# BlaszczakPI.net
KiCad netlist of a schematic drawn in EAGLE
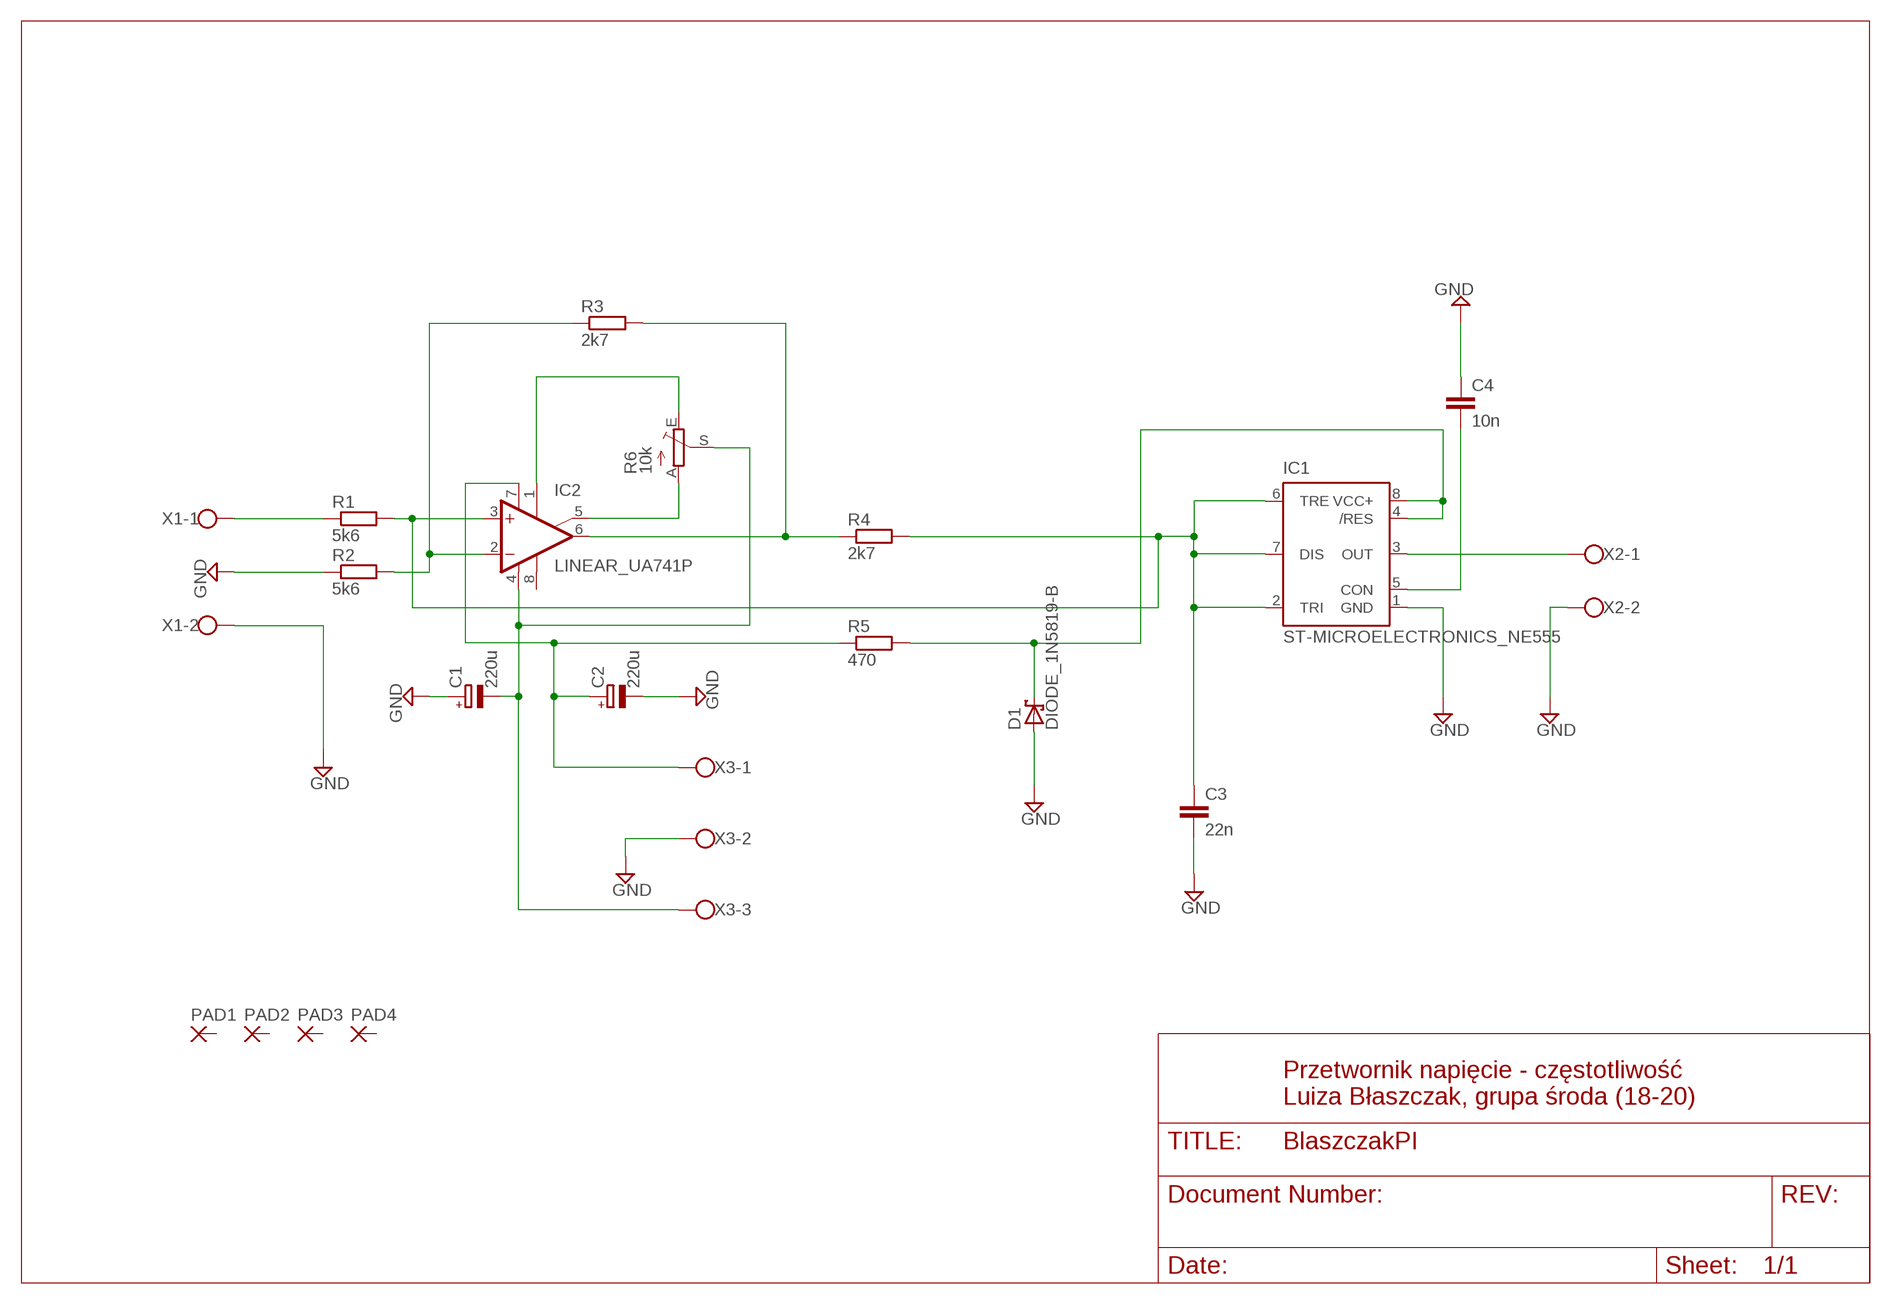
[diagram p0: schematic, sheet 1]

(export (version "E")
  (design (tool "Eeschema 10.0.6"))
  (components
    (comp (ref "C1")
      (value "220u")
      (footprint "eagle-import:RCL_E2,5-7")
      (libsource (lib "eagle-import") (part "RCL_CPOL-EUE2.5-7"))
    )
    (comp (ref "C2")
      (value "220u")
      (footprint "eagle-import:RCL_E2,5-7")
      (libsource (lib "eagle-import") (part "RCL_CPOL-EUE2.5-7"))
    )
    (comp (ref "C3")
      (value "22n")
      (footprint "eagle-import:C1206")
      (libsource (lib "eagle-import") (part "C-EUC1206"))
    )
    (comp (ref "C4")
      (value "10n")
      (footprint "eagle-import:C1206")
      (libsource (lib "eagle-import") (part "C-EUC1206"))
    )
    (comp (ref "D1")
      (value "DIODE_1N5819-B")
      (footprint "eagle-import:DIODE_DO41-7.6")
      (libsource (lib "eagle-import") (part "DIODE_1N5819-B"))
    )
    (comp (ref "IC1")
      (value "ST-MICROELECTRONICS_NE555")
      (footprint "eagle-import:ST-MICROELECTRONICS_DIL-08")
      (fields (field (name "MF") "Arrow Electronics") (field (name "MPN") "NE555N"))
      (libsource (lib "eagle-import") (part "ST-MICROELECTRONICS_NE555"))
    )
    (comp (ref "IC2")
      (value "LINEAR_UA741P")
      (footprint "eagle-import:LINEAR_DIL08")
      (libsource (lib "eagle-import") (part "LINEAR_741PUA"))
    )
    (comp (ref "PAD1")
      (value "2,54/1,1")
      (footprint "eagle-import:2,54_1,1")
      (libsource (lib "eagle-import") (part "2,54/1,1"))
    )
    (comp (ref "PAD2")
      (value "2,54/1,1")
      (footprint "eagle-import:2,54_1,1")
      (libsource (lib "eagle-import") (part "2,54/1,1"))
    )
    (comp (ref "PAD3")
      (value "2,54/1,1")
      (footprint "eagle-import:2,54_1,1")
      (libsource (lib "eagle-import") (part "2,54/1,1"))
    )
    (comp (ref "PAD4")
      (value "2,54/1,1")
      (footprint "eagle-import:2,54_1,1")
      (libsource (lib "eagle-import") (part "2,54/1,1"))
    )
    (comp (ref "R1")
      (value "5k6")
      (footprint "eagle-import:M1206")
      (libsource (lib "eagle-import") (part "R-EU_M1206"))
    )
    (comp (ref "R2")
      (value "5k6")
      (footprint "eagle-import:M1206")
      (libsource (lib "eagle-import") (part "R-EU_M1206"))
    )
    (comp (ref "R3")
      (value "2k7")
      (footprint "eagle-import:M1206")
      (libsource (lib "eagle-import") (part "R-EU_M1206"))
    )
    (comp (ref "R4")
      (value "2k7")
      (footprint "eagle-import:M1206")
      (libsource (lib "eagle-import") (part "R-EU_M1206"))
    )
    (comp (ref "R5")
      (value "470")
      (footprint "eagle-import:M1206")
      (libsource (lib "eagle-import") (part "R-EU_M1206"))
    )
    (comp (ref "R6")
      (value "10k")
      (footprint "eagle-import:POT_CA6V")
      (libsource (lib "eagle-import") (part "POT_TRIM_EU-CA6V"))
    )
    (comp (ref "X1")
      (value "CON-WAGO-500_W237-102")
      (footprint "eagle-import:CON-WAGO-500_W237-102")
      (fields (field (name "MPN") "237-102"))
      (libsource (lib "eagle-import") (part "CON-WAGO-500_W237-102"))
    )
    (comp (ref "X2")
      (value "CON-WAGO-500_W237-102")
      (footprint "eagle-import:CON-WAGO-500_W237-102")
      (fields (field (name "MPN") "237-102"))
      (libsource (lib "eagle-import") (part "CON-WAGO-500_W237-102"))
    )
    (comp (ref "X3")
      (value "CON-WAGO-500_W237-103")
      (footprint "eagle-import:CON-WAGO-500_W237-103")
      (fields (field (name "MPN") "237-103"))
      (libsource (lib "eagle-import") (part "CON-WAGO-500_W237-103"))
    )
  )
  (nets
    (net (code "1") (name "GND") (class "Default")
      (node (ref "C1") (pin "+") (pinfunction "+_+") (pintype "passive"))
      (node (ref "C2") (pin "-") (pinfunction "-_-") (pintype "passive"))
      (node (ref "C3") (pin "2") (pinfunction "2_2") (pintype "passive"))
      (node (ref "C4") (pin "1") (pinfunction "1_1") (pintype "passive"))
      (node (ref "D1") (pin "A") (pinfunction "A_A") (pintype "passive"))
      (node (ref "IC1") (pin "1") (pinfunction "GND_1") (pintype "power_in"))
      (node (ref "R2") (pin "1") (pinfunction "1_1") (pintype "passive"))
      (node (ref "X1") (pin "2") (pinfunction "KL_2") (pintype "passive"))
      (node (ref "X2") (pin "2") (pinfunction "KL_2") (pintype "passive"))
      (node (ref "X3") (pin "2") (pinfunction "KL_2") (pintype "passive"))
    )
    (net (code "2") (name "Net-(IC1-CON)") (class "Default")
      (node (ref "C4") (pin "2") (pinfunction "2_2") (pintype "passive"))
      (node (ref "IC1") (pin "5") (pinfunction "CON_5") (pintype "input"))
    )
    (net (code "3") (name "Net-(IC1-DIS)") (class "Default")
      (node (ref "C3") (pin "1") (pinfunction "1_1") (pintype "passive"))
      (node (ref "IC1") (pin "2") (pinfunction "TRI_2") (pintype "input"))
      (node (ref "IC1") (pin "6") (pinfunction "TRE_6") (pintype "input"))
      (node (ref "IC1") (pin "7") (pinfunction "DIS_7") (pintype "input"))
      (node (ref "IC2") (pin "3") (pinfunction "+IN_3") (pintype "input"))
      (node (ref "R1") (pin "2") (pinfunction "2_2") (pintype "passive"))
      (node (ref "R4") (pin "2") (pinfunction "2_2") (pintype "passive"))
    )
    (net (code "4") (name "Net-(IC1-OUT)") (class "Default")
      (node (ref "IC1") (pin "3") (pinfunction "OUT_3") (pintype "output"))
      (node (ref "X2") (pin "1") (pinfunction "KL_1") (pintype "passive"))
    )
    (net (code "5") (name "Net-(IC1-VCC+)") (class "Default")
      (node (ref "D1") (pin "C") (pinfunction "C_C") (pintype "passive"))
      (node (ref "IC1") (pin "4") (pinfunction "/RES_4") (pintype "input"))
      (node (ref "IC1") (pin "8") (pinfunction "VCC+_8") (pintype "power_in"))
      (node (ref "R5") (pin "2") (pinfunction "2_2") (pintype "passive"))
    )
    (net (code "6") (name "Net-(IC2--IN)") (class "Default")
      (node (ref "IC2") (pin "2") (pinfunction "-IN_2") (pintype "input"))
      (node (ref "R2") (pin "2") (pinfunction "2_2") (pintype "passive"))
      (node (ref "R3") (pin "1") (pinfunction "1_1") (pintype "passive"))
    )
    (net (code "7") (name "Net-(IC2-ON1)") (class "Default")
      (node (ref "IC2") (pin "1") (pinfunction "ON1_1") (pintype "passive"))
      (node (ref "R6") (pin "E") (pinfunction "E_E") (pintype "passive"))
    )
    (net (code "8") (name "Net-(IC2-ON2)") (class "Default")
      (node (ref "IC2") (pin "5") (pinfunction "ON2_5") (pintype "passive"))
      (node (ref "R6") (pin "A") (pinfunction "A_A") (pintype "passive"))
    )
    (net (code "9") (name "Net-(IC2-OUT)") (class "Default")
      (node (ref "IC2") (pin "6") (pinfunction "OUT_6") (pintype "output"))
      (node (ref "R3") (pin "2") (pinfunction "2_2") (pintype "passive"))
      (node (ref "R4") (pin "1") (pinfunction "1_1") (pintype "passive"))
    )
    (net (code "10") (name "Net-(IC2-V+)") (class "Default")
      (node (ref "C2") (pin "+") (pinfunction "+_+") (pintype "passive"))
      (node (ref "IC2") (pin "7") (pinfunction "V+_7") (pintype "power_in"))
      (node (ref "R5") (pin "1") (pinfunction "1_1") (pintype "passive"))
      (node (ref "X3") (pin "1") (pinfunction "KL_1") (pintype "passive"))
    )
    (net (code "11") (name "Net-(IC2-V-)") (class "Default")
      (node (ref "C1") (pin "-") (pinfunction "-_-") (pintype "passive"))
      (node (ref "IC2") (pin "4") (pinfunction "V-_4") (pintype "power_in"))
      (node (ref "R6") (pin "S") (pinfunction "S_S") (pintype "passive"))
      (node (ref "X3") (pin "3") (pinfunction "KL_3") (pintype "passive"))
    )
    (net (code "12") (name "Net-(X1A-KL)") (class "Default")
      (node (ref "R1") (pin "1") (pinfunction "1_1") (pintype "passive"))
      (node (ref "X1") (pin "1") (pinfunction "KL_1") (pintype "passive"))
    )
    (net (code "13") (name "unconnected-(IC2-OPT-Pad8)") (class "Default")
      (node (ref "IC2") (pin "8") (pinfunction "OPT_8") (pintype "passive"))
    )
    (net (code "14") (name "unconnected-(PAD1-P-Pad1)") (class "Default")
      (node (ref "PAD1") (pin "1") (pinfunction "P_1") (pintype "passive"))
    )
    (net (code "15") (name "unconnected-(PAD2-P-Pad1)") (class "Default")
      (node (ref "PAD2") (pin "1") (pinfunction "P_1") (pintype "passive"))
    )
    (net (code "16") (name "unconnected-(PAD3-P-Pad1)") (class "Default")
      (node (ref "PAD3") (pin "1") (pinfunction "P_1") (pintype "passive"))
    )
    (net (code "17") (name "unconnected-(PAD4-P-Pad1)") (class "Default")
      (node (ref "PAD4") (pin "1") (pinfunction "P_1") (pintype "passive"))
    )
  )
)
